# SparkFunVKeyVoltageKeypad.net
KiCad netlist of a schematic drawn in EAGLE
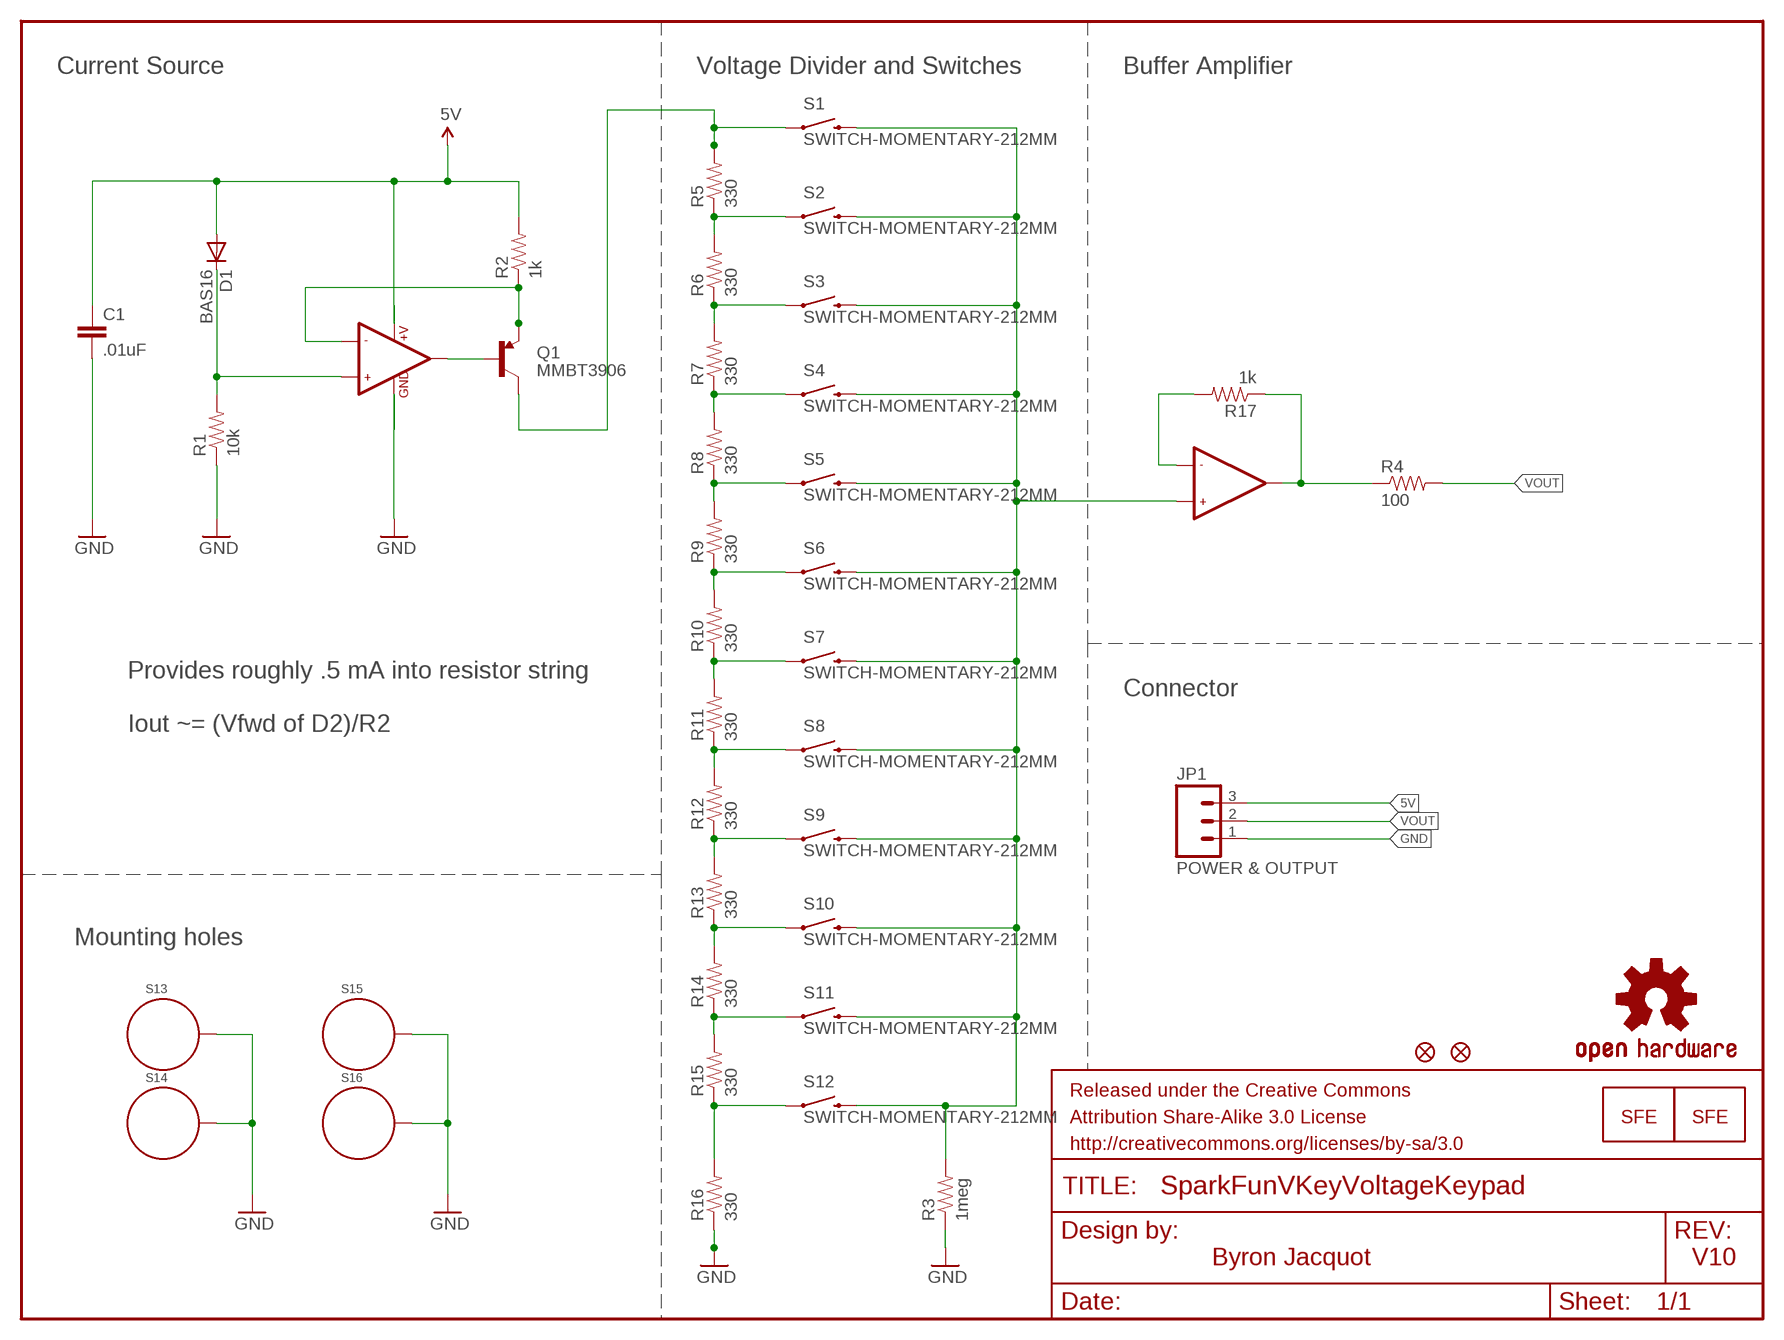
[diagram p0: schematic, sheet 1]

(export (version "E")
  (design (tool "Eeschema 10.0.6"))
  (components
    (comp (ref "C1")
      (value ".01uF")
      (footprint "eagle-import:0603-CAP")
      (libsource (lib "eagle-import") (part "10NF/10000PF-50V-10%(0603)"))
    )
    (comp (ref "D1")
      (value "BAS16")
      (footprint "eagle-import:SOD-323")
      (libsource (lib "eagle-import") (part "DIODESOD"))
    )
    (comp (ref "FID1")
      (value "FIDUCIALUFIDUCIAL")
      (footprint "eagle-import:MICRO-FIDUCIAL")
      (libsource (lib "eagle-import") (part "FIDUCIALUFIDUCIAL"))
    )
    (comp (ref "FID2")
      (value "FIDUCIALUFIDUCIAL")
      (footprint "eagle-import:MICRO-FIDUCIAL")
      (libsource (lib "eagle-import") (part "FIDUCIALUFIDUCIAL"))
    )
    (comp (ref "FRAME1")
      (value "FRAME-LETTER")
      (footprint "eagle-import:CREATIVE_COMMONS")
      (libsource (lib "eagle-import") (part "FRAME-LETTER"))
    )
    (comp (ref "JP1")
      (value "POWER & OUTPUT")
      (footprint "eagle-import:1X03_NO_SILK")
      (libsource (lib "eagle-import") (part "M031X03_NO_SILK"))
    )
    (comp (ref "LOGO1")
      (value "LOGO-SFENEW")
      (footprint "eagle-import:SFE-NEW-WEBLOGO")
      (libsource (lib "eagle-import") (part "LOGO-SFENEW"))
    )
    (comp (ref "LOGO2")
      (value "LOGO-SFENEW")
      (footprint "eagle-import:SFE-NEW-WEBLOGO")
      (libsource (lib "eagle-import") (part "LOGO-SFENEW"))
    )
    (comp (ref "LOGO3")
      (value "OSHW-LOGOM")
      (footprint "eagle-import:OSHW-LOGO-M")
      (libsource (lib "eagle-import") (part "OSHW-LOGOM"))
    )
    (comp (ref "LOGO4")
      (value "OSHW-LOGOL")
      (footprint "eagle-import:OSHW-LOGO-L")
      (libsource (lib "eagle-import") (part "OSHW-LOGOL"))
    )
    (comp (ref "Q1")
      (value "MMBT3906")
      (footprint "eagle-import:SOT23")
      (libsource (lib "eagle-import") (part "TRANSISTOR_PNPMMBT3906"))
    )
    (comp (ref "R1")
      (value "10k")
      (footprint "eagle-import:0603-RES")
      (libsource (lib "eagle-import") (part "10KOHM1/10W1%(0603)0603"))
    )
    (comp (ref "R2")
      (value "1k")
      (footprint "eagle-import:0603-RES")
      (libsource (lib "eagle-import") (part "1KOHM1/10W1%(0603)"))
    )
    (comp (ref "R3")
      (value "1meg")
      (footprint "eagle-import:0603-RES")
      (libsource (lib "eagle-import") (part "1M-1%"))
    )
    (comp (ref "R4")
      (value "100")
      (footprint "eagle-import:0603-RES")
      (libsource (lib "eagle-import") (part "100OHM1/10W1%(0603)"))
    )
    (comp (ref "R5")
      (value "330")
      (footprint "eagle-import:0603-RES")
      (libsource (lib "eagle-import") (part "330OHM1/10W1%(0603)"))
    )
    (comp (ref "R6")
      (value "330")
      (footprint "eagle-import:0603-RES")
      (fields (field (name "PROD_ID") "RES-00818"))
      (libsource (lib "eagle-import") (part "330OHM1/10W1%(0603)"))
    )
    (comp (ref "R7")
      (value "330")
      (footprint "eagle-import:0603-RES")
      (fields (field (name "PROD_ID") "RES-00818"))
      (libsource (lib "eagle-import") (part "330OHM1/10W1%(0603)"))
    )
    (comp (ref "R8")
      (value "330")
      (footprint "eagle-import:0603-RES")
      (fields (field (name "PROD_ID") "RES-00818"))
      (libsource (lib "eagle-import") (part "330OHM1/10W1%(0603)"))
    )
    (comp (ref "R9")
      (value "330")
      (footprint "eagle-import:0603-RES")
      (fields (field (name "PROD_ID") "RES-00818"))
      (libsource (lib "eagle-import") (part "330OHM1/10W1%(0603)"))
    )
    (comp (ref "R10")
      (value "330")
      (footprint "eagle-import:0603-RES")
      (fields (field (name "PROD_ID") "RES-00818"))
      (libsource (lib "eagle-import") (part "330OHM1/10W1%(0603)"))
    )
    (comp (ref "R11")
      (value "330")
      (footprint "eagle-import:0603-RES")
      (fields (field (name "PROD_ID") "RES-00818"))
      (libsource (lib "eagle-import") (part "330OHM1/10W1%(0603)"))
    )
    (comp (ref "R12")
      (value "330")
      (footprint "eagle-import:0603-RES")
      (fields (field (name "PROD_ID") "RES-00818"))
      (libsource (lib "eagle-import") (part "330OHM1/10W1%(0603)"))
    )
    (comp (ref "R13")
      (value "330")
      (footprint "eagle-import:0603-RES")
      (fields (field (name "PROD_ID") "RES-00818"))
      (libsource (lib "eagle-import") (part "330OHM1/10W1%(0603)"))
    )
    (comp (ref "R14")
      (value "330")
      (footprint "eagle-import:0603-RES")
      (fields (field (name "PROD_ID") "RES-00818"))
      (libsource (lib "eagle-import") (part "330OHM1/10W1%(0603)"))
    )
    (comp (ref "R15")
      (value "330")
      (footprint "eagle-import:0603-RES")
      (fields (field (name "PROD_ID") "RES-00818"))
      (libsource (lib "eagle-import") (part "330OHM1/10W1%(0603)"))
    )
    (comp (ref "R16")
      (value "330")
      (footprint "eagle-import:0603-RES")
      (fields (field (name "PROD_ID") "RES-00818"))
      (libsource (lib "eagle-import") (part "330OHM1/10W1%(0603)"))
    )
    (comp (ref "R17")
      (value "1k")
      (footprint "eagle-import:0603-RES")
      (libsource (lib "eagle-import") (part "1KOHM1/10W1%(0603)"))
    )
    (comp (ref "S1")
      (value "SWITCH-MOMENTARY-212MM")
      (footprint "eagle-import:TACTILE-PTH-12MM")
      (libsource (lib "eagle-import") (part "SWITCH-MOMENTARY-212MM"))
    )
    (comp (ref "S2")
      (value "SWITCH-MOMENTARY-212MM")
      (footprint "eagle-import:TACTILE-PTH-12MM")
      (libsource (lib "eagle-import") (part "SWITCH-MOMENTARY-212MM"))
    )
    (comp (ref "S3")
      (value "SWITCH-MOMENTARY-212MM")
      (footprint "eagle-import:TACTILE-PTH-12MM")
      (libsource (lib "eagle-import") (part "SWITCH-MOMENTARY-212MM"))
    )
    (comp (ref "S4")
      (value "SWITCH-MOMENTARY-212MM")
      (footprint "eagle-import:TACTILE-PTH-12MM")
      (libsource (lib "eagle-import") (part "SWITCH-MOMENTARY-212MM"))
    )
    (comp (ref "S5")
      (value "SWITCH-MOMENTARY-212MM")
      (footprint "eagle-import:TACTILE-PTH-12MM")
      (libsource (lib "eagle-import") (part "SWITCH-MOMENTARY-212MM"))
    )
    (comp (ref "S6")
      (value "SWITCH-MOMENTARY-212MM")
      (footprint "eagle-import:TACTILE-PTH-12MM")
      (libsource (lib "eagle-import") (part "SWITCH-MOMENTARY-212MM"))
    )
    (comp (ref "S7")
      (value "SWITCH-MOMENTARY-212MM")
      (footprint "eagle-import:TACTILE-PTH-12MM")
      (libsource (lib "eagle-import") (part "SWITCH-MOMENTARY-212MM"))
    )
    (comp (ref "S8")
      (value "SWITCH-MOMENTARY-212MM")
      (footprint "eagle-import:TACTILE-PTH-12MM")
      (libsource (lib "eagle-import") (part "SWITCH-MOMENTARY-212MM"))
    )
    (comp (ref "S9")
      (value "SWITCH-MOMENTARY-212MM")
      (footprint "eagle-import:TACTILE-PTH-12MM")
      (libsource (lib "eagle-import") (part "SWITCH-MOMENTARY-212MM"))
    )
    (comp (ref "S10")
      (value "SWITCH-MOMENTARY-212MM")
      (footprint "eagle-import:TACTILE-PTH-12MM")
      (libsource (lib "eagle-import") (part "SWITCH-MOMENTARY-212MM"))
    )
    (comp (ref "S11")
      (value "SWITCH-MOMENTARY-212MM")
      (footprint "eagle-import:TACTILE-PTH-12MM")
      (libsource (lib "eagle-import") (part "SWITCH-MOMENTARY-212MM"))
    )
    (comp (ref "S12")
      (value "SWITCH-MOMENTARY-212MM")
      (footprint "eagle-import:TACTILE-PTH-12MM")
      (libsource (lib "eagle-import") (part "SWITCH-MOMENTARY-212MM"))
    )
    (comp (ref "S13")
      (value "STANDOFF_ELECTRICAL")
      (footprint "eagle-import:STANDOFF-ELECTRICAL")
      (libsource (lib "eagle-import") (part "STANDOFF_ELECTRICAL"))
    )
    (comp (ref "S14")
      (value "STANDOFF_ELECTRICAL")
      (footprint "eagle-import:STANDOFF-ELECTRICAL")
      (libsource (lib "eagle-import") (part "STANDOFF_ELECTRICAL"))
    )
    (comp (ref "S15")
      (value "STANDOFF_ELECTRICAL")
      (footprint "eagle-import:STANDOFF-ELECTRICAL")
      (libsource (lib "eagle-import") (part "STANDOFF_ELECTRICAL"))
    )
    (comp (ref "S16")
      (value "STANDOFF_ELECTRICAL")
      (footprint "eagle-import:STANDOFF-ELECTRICAL")
      (libsource (lib "eagle-import") (part "STANDOFF_ELECTRICAL"))
    )
    (comp (ref "U1")
      (value "LMV358")
      (footprint "eagle-import:SO08")
      (libsource (lib "eagle-import") (part "LMV358"))
    )
  )
  (nets
    (net (code "1") (name "5V") (class "Default")
      (node (ref "C1") (pin "1") (pinfunction "1_1") (pintype "passive"))
      (node (ref "D1") (pin "2") (pinfunction "A_2") (pintype "passive"))
      (node (ref "JP1") (pin "3") (pinfunction "3_3") (pintype "passive"))
      (node (ref "R2") (pin "2") (pinfunction "2_2") (pintype "passive"))
      (node (ref "U1") (pin "8") (pinfunction "+V_8") (pintype "power_in"))
    )
    (net (code "2") (name "GND") (class "Default")
      (node (ref "C1") (pin "2") (pinfunction "2_2") (pintype "passive"))
      (node (ref "JP1") (pin "1") (pinfunction "1_1") (pintype "passive"))
      (node (ref "R1") (pin "1") (pinfunction "1_1") (pintype "passive"))
      (node (ref "R16") (pin "1") (pinfunction "1_1") (pintype "passive"))
      (node (ref "R3") (pin "1") (pinfunction "1_1") (pintype "passive"))
      (node (ref "S13") (pin "P1") (pinfunction "P$1_P1") (pintype "bidirectional"))
      (node (ref "S14") (pin "P1") (pinfunction "P$1_P1") (pintype "bidirectional"))
      (node (ref "S15") (pin "P1") (pinfunction "P$1_P1") (pintype "bidirectional"))
      (node (ref "S16") (pin "P1") (pinfunction "P$1_P1") (pintype "bidirectional"))
      (node (ref "U1") (pin "4") (pinfunction "GND_4") (pintype "power_in"))
    )
    (net (code "3") (name "Net-(D1-C)") (class "Default")
      (node (ref "D1") (pin "1") (pinfunction "C_1") (pintype "passive"))
      (node (ref "R1") (pin "2") (pinfunction "2_2") (pintype "passive"))
      (node (ref "U1") (pin "3") (pinfunction "+IN1_3") (pintype "input"))
    )
    (net (code "4") (name "Net-(Q1-B)") (class "Default")
      (node (ref "Q1") (pin "1") (pinfunction "B_1") (pintype "passive"))
      (node (ref "U1") (pin "1") (pinfunction "OUT1_1") (pintype "output"))
    )
    (net (code "5") (name "Net-(Q1-C)") (class "Default")
      (node (ref "Q1") (pin "3") (pinfunction "C_3") (pintype "passive"))
      (node (ref "R5") (pin "2") (pinfunction "2_2") (pintype "passive"))
      (node (ref "S1") (pin "1") (pinfunction "1_1") (pintype "passive"))
    )
    (net (code "6") (name "Net-(Q1-E)") (class "Default")
      (node (ref "Q1") (pin "2") (pinfunction "E_2") (pintype "passive"))
      (node (ref "R2") (pin "1") (pinfunction "1_1") (pintype "passive"))
      (node (ref "U1") (pin "2") (pinfunction "-IN1_2") (pintype "input"))
    )
    (net (code "7") (name "Net-(R5-Pad1)") (class "Default")
      (node (ref "R5") (pin "1") (pinfunction "1_1") (pintype "passive"))
      (node (ref "R6") (pin "2") (pinfunction "2_2") (pintype "passive"))
      (node (ref "S2") (pin "1") (pinfunction "1_1") (pintype "passive"))
    )
    (net (code "8") (name "Net-(R6-Pad1)") (class "Default")
      (node (ref "R6") (pin "1") (pinfunction "1_1") (pintype "passive"))
      (node (ref "R7") (pin "2") (pinfunction "2_2") (pintype "passive"))
      (node (ref "S3") (pin "1") (pinfunction "1_1") (pintype "passive"))
    )
    (net (code "9") (name "Net-(R7-Pad1)") (class "Default")
      (node (ref "R7") (pin "1") (pinfunction "1_1") (pintype "passive"))
      (node (ref "R8") (pin "2") (pinfunction "2_2") (pintype "passive"))
      (node (ref "S4") (pin "1") (pinfunction "1_1") (pintype "passive"))
    )
    (net (code "10") (name "Net-(R8-Pad1)") (class "Default")
      (node (ref "R8") (pin "1") (pinfunction "1_1") (pintype "passive"))
      (node (ref "R9") (pin "2") (pinfunction "2_2") (pintype "passive"))
      (node (ref "S5") (pin "1") (pinfunction "1_1") (pintype "passive"))
    )
    (net (code "11") (name "Net-(R10-Pad1)") (class "Default")
      (node (ref "R10") (pin "1") (pinfunction "1_1") (pintype "passive"))
      (node (ref "R11") (pin "2") (pinfunction "2_2") (pintype "passive"))
      (node (ref "S7") (pin "1") (pinfunction "1_1") (pintype "passive"))
    )
    (net (code "12") (name "Net-(R10-Pad2)") (class "Default")
      (node (ref "R10") (pin "2") (pinfunction "2_2") (pintype "passive"))
      (node (ref "R9") (pin "1") (pinfunction "1_1") (pintype "passive"))
      (node (ref "S6") (pin "1") (pinfunction "1_1") (pintype "passive"))
    )
    (net (code "13") (name "Net-(R11-Pad1)") (class "Default")
      (node (ref "R11") (pin "1") (pinfunction "1_1") (pintype "passive"))
      (node (ref "R12") (pin "2") (pinfunction "2_2") (pintype "passive"))
      (node (ref "S8") (pin "1") (pinfunction "1_1") (pintype "passive"))
    )
    (net (code "14") (name "Net-(R12-Pad1)") (class "Default")
      (node (ref "R12") (pin "1") (pinfunction "1_1") (pintype "passive"))
      (node (ref "R13") (pin "2") (pinfunction "2_2") (pintype "passive"))
      (node (ref "S9") (pin "1") (pinfunction "1_1") (pintype "passive"))
    )
    (net (code "15") (name "Net-(R13-Pad1)") (class "Default")
      (node (ref "R13") (pin "1") (pinfunction "1_1") (pintype "passive"))
      (node (ref "R14") (pin "2") (pinfunction "2_2") (pintype "passive"))
      (node (ref "S10") (pin "1") (pinfunction "1_1") (pintype "passive"))
    )
    (net (code "16") (name "Net-(R14-Pad1)") (class "Default")
      (node (ref "R14") (pin "1") (pinfunction "1_1") (pintype "passive"))
      (node (ref "R15") (pin "2") (pinfunction "2_2") (pintype "passive"))
      (node (ref "S11") (pin "1") (pinfunction "1_1") (pintype "passive"))
    )
    (net (code "17") (name "Net-(R15-Pad1)") (class "Default")
      (node (ref "R15") (pin "1") (pinfunction "1_1") (pintype "passive"))
      (node (ref "R16") (pin "2") (pinfunction "2_2") (pintype "passive"))
      (node (ref "S12") (pin "1") (pinfunction "1_1") (pintype "passive"))
    )
    (net (code "18") (name "Net-(S1-2)") (class "Default")
      (node (ref "R3") (pin "2") (pinfunction "2_2") (pintype "passive"))
      (node (ref "S1") (pin "3") (pinfunction "2_3") (pintype "passive"))
      (node (ref "S10") (pin "3") (pinfunction "2_3") (pintype "passive"))
      (node (ref "S11") (pin "3") (pinfunction "2_3") (pintype "passive"))
      (node (ref "S12") (pin "3") (pinfunction "2_3") (pintype "passive"))
      (node (ref "S2") (pin "3") (pinfunction "2_3") (pintype "passive"))
      (node (ref "S3") (pin "3") (pinfunction "2_3") (pintype "passive"))
      (node (ref "S4") (pin "3") (pinfunction "2_3") (pintype "passive"))
      (node (ref "S5") (pin "3") (pinfunction "2_3") (pintype "passive"))
      (node (ref "S6") (pin "3") (pinfunction "2_3") (pintype "passive"))
      (node (ref "S7") (pin "3") (pinfunction "2_3") (pintype "passive"))
      (node (ref "S8") (pin "3") (pinfunction "2_3") (pintype "passive"))
      (node (ref "S9") (pin "3") (pinfunction "2_3") (pintype "passive"))
      (node (ref "U1") (pin "5") (pinfunction "+IN2_5") (pintype "input"))
    )
    (net (code "19") (name "Net-(U1B--IN2)") (class "Default")
      (node (ref "R17") (pin "2") (pinfunction "2_2") (pintype "passive"))
      (node (ref "U1") (pin "6") (pinfunction "-IN2_6") (pintype "input"))
    )
    (net (code "20") (name "Net-(U1B-OUT2)") (class "Default")
      (node (ref "R17") (pin "1") (pinfunction "1_1") (pintype "passive"))
      (node (ref "R4") (pin "1") (pinfunction "1_1") (pintype "passive"))
      (node (ref "U1") (pin "7") (pinfunction "OUT2_7") (pintype "output"))
    )
    (net (code "21") (name "VOUT") (class "Default")
      (node (ref "JP1") (pin "2") (pinfunction "2_2") (pintype "passive"))
      (node (ref "R4") (pin "2") (pinfunction "2_2") (pintype "passive"))
    )
  )
)
